# Power_-_1V2.net
KiCad netlist of a schematic drawn in Altium Designer
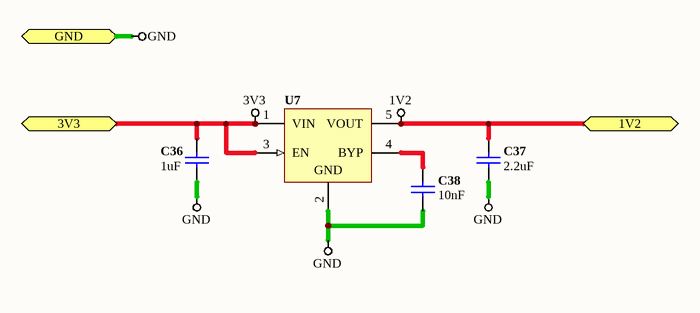
[diagram p0: Power - 1V2_.SchDoc]

(export (version "E")
  (design (tool "Eeschema 10.0.6"))
  (components
    (comp (ref "C36")
      (value "1uF")
      (footprint "CAPC0402(1005)60_L")
      (description "CAP 1uF 16V ±10% 0402 (1005 Metric) Thickness 0.6mm SMD")
      (fields
        (field (name "TOLERANCE") "±10%")
        (field (name "MANUFACTURER PART NUMBER") "C1005X5R1C105K050BC")
      )
      (libsource (lib "Altium Content Vault") (part "CMP-1034-02119-1"))
    )
    (comp (ref "C37")
      (value "2.2uF")
      (footprint "CAPC0603(1608)55_L")
      (description "CAP 2.2uF 16V ±10% 0603 (1608 Metric) Thickness 0.55mm SMD")
      (fields (field (name "TOLERANCE") "±10%") (field (name "MANUFACTURER PART NUMBER") "C0603C225K4PACTU"))
      (libsource (lib "Altium Content Vault") (part "CMP-1035-02762-1"))
    )
    (comp (ref "C38")
      (value "10nF")
      (footprint "CAPC0402(1005)33_L")
      (description "CAP 10nF 16V ±10% 0402 (1005 Metric) Thickness 0.33mm SMD")
      (fields
        (field (name "TOLERANCE") "±10%")
        (field (name "MANUFACTURER PART NUMBER") "GRM155R61C103KA01D")
      )
      (libsource (lib "Altium Content Vault") (part "CMP-1034-01875-1"))
    )
    (comp (ref "U7")
      (value "CAT6219-125TDGT3")
      (footprint "ONSC-SOT23-5_M")
      (description "Fixed Low Drop Positive Voltage Regulator, 1.2V 5-Pin TSOT-23, Tape and Reel")
      (fields (field (name "PARTNUMBER") "CAT6219-330TDGT3") (field (name "MANUFACTURER") "ON Semiconductor"))
      (libsource (lib "CAT6219-125TDGT3") (part "CAT6219-125TDGT3"))
    )
  )
  (nets
    (net (code "1") (name "1V2") (class "Default")
      (node (ref "C37") (pin "2") (pinfunction "2_2") (pintype "passive"))
      (node (ref "U7") (pin "5") (pinfunction "VOUT_5") (pintype "power_in"))
    )
    (net (code "2") (name "3V3") (class "Default")
      (node (ref "C36") (pin "2") (pinfunction "2_2") (pintype "passive"))
      (node (ref "U7") (pin "1") (pinfunction "VIN_1") (pintype "power_in"))
      (node (ref "U7") (pin "3") (pinfunction "EN_3") (pintype "input"))
    )
    (net (code "3") (name "GND") (class "Default")
      (node (ref "C36") (pin "1") (pinfunction "1_1") (pintype "passive"))
      (node (ref "C37") (pin "1") (pinfunction "1_1") (pintype "passive"))
      (node (ref "C38") (pin "1") (pinfunction "1_1") (pintype "passive"))
      (node (ref "U7") (pin "2") (pinfunction "GND_2") (pintype "power_in"))
    )
    (net (code "4") (name "Net-(U7-BYP)") (class "Default")
      (node (ref "C38") (pin "2") (pinfunction "2_2") (pintype "passive"))
      (node (ref "U7") (pin "4") (pinfunction "BYP_4") (pintype "passive"))
    )
  )
)
